# watch_v1_light-addon.net
KiCad netlist of a schematic drawn in EAGLE
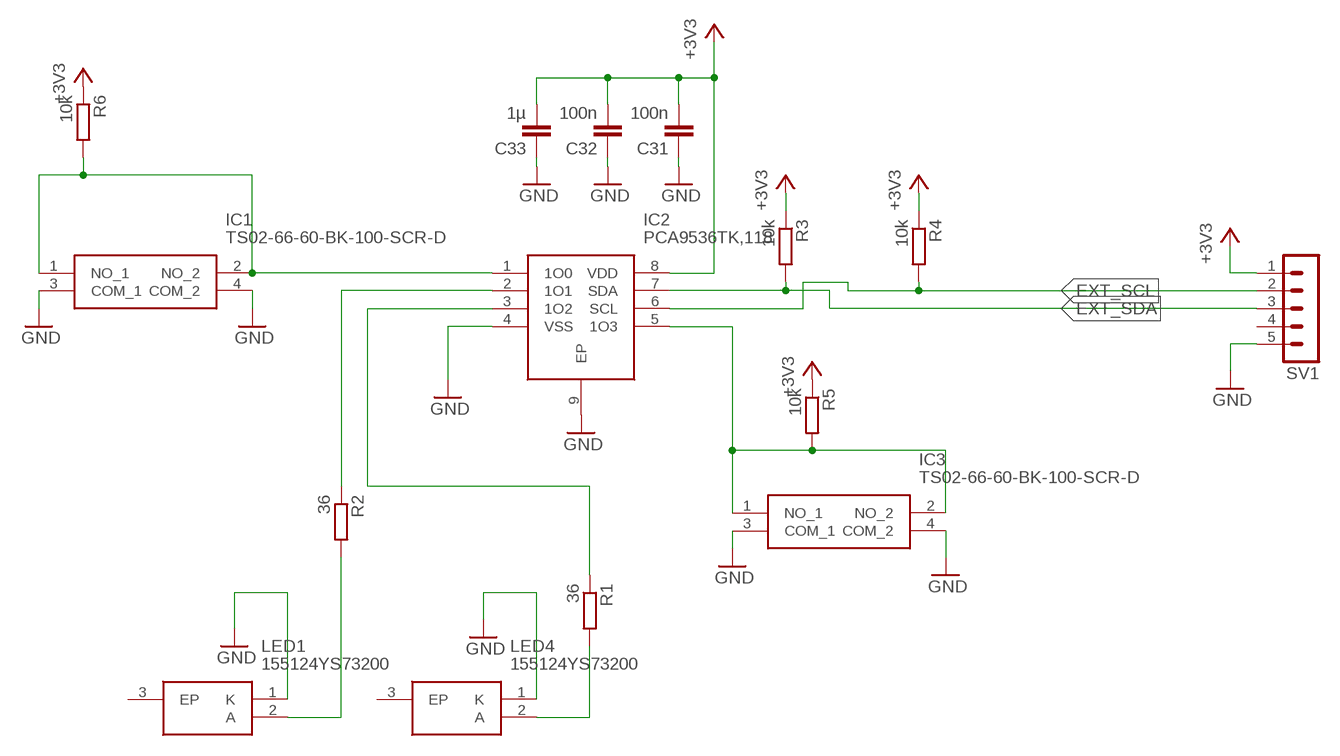
[diagram p0: schematic, sheet 1]

(export (version "E")
  (design (tool "Eeschema 10.0.6"))
  (components
    (comp (ref "C31")
      (value "100n")
      (footprint "eagle-import:C0402_S")
      (libsource (lib "eagle-import") (part "C0402_S"))
    )
    (comp (ref "C32")
      (value "100n")
      (footprint "eagle-import:C0402_S")
      (libsource (lib "eagle-import") (part "C0402_S"))
    )
    (comp (ref "C33")
      (value "1µ")
      (footprint "eagle-import:C0402_S")
      (libsource (lib "eagle-import") (part "C0402_S"))
    )
    (comp (ref "IC1")
      (value "TS02-66-60-BK-100-SCR-D")
      (footprint "eagle-import:TS026660BK100SCRD")
      (fields (field (name "MOUSER_PART_NUMBER") "179-TS026660BK100SCR"))
      (libsource (lib "eagle-import") (part "TS02-66-60-BK-100-SCR-D"))
    )
    (comp (ref "IC2")
      (value "PCA9536TK,118")
      (footprint "eagle-import:SON50P300X300X100-9N")
      (fields (field (name "MOUSER_PART_NUMBER") "771-PCA9536TK118"))
      (libsource (lib "eagle-import") (part "PCA9536TK,118"))
    )
    (comp (ref "IC3")
      (value "TS02-66-60-BK-100-SCR-D")
      (footprint "eagle-import:TS026660BK100SCRD")
      (fields (field (name "MOUSER_PART_NUMBER") "179-TS026660BK100SCR"))
      (libsource (lib "eagle-import") (part "TS02-66-60-BK-100-SCR-D"))
    )
    (comp (ref "LED1")
      (value "155124YS73200")
      (footprint "eagle-import:155124YS73200")
      (fields (field (name "MOUSER_PART_NUMBER") "710-155124YS73200"))
      (libsource (lib "eagle-import") (part "155124YS73200"))
    )
    (comp (ref "LED4")
      (value "155124YS73200")
      (footprint "eagle-import:155124YS73200")
      (fields (field (name "MOUSER_PART_NUMBER") "710-155124YS73200"))
      (libsource (lib "eagle-import") (part "155124YS73200"))
    )
    (comp (ref "R1")
      (value "36")
      (footprint "eagle-import:R0402")
      (libsource (lib "eagle-import") (part "R0402"))
    )
    (comp (ref "R2")
      (value "36")
      (footprint "eagle-import:R0402")
      (libsource (lib "eagle-import") (part "R0402"))
    )
    (comp (ref "R3")
      (value "10k")
      (footprint "eagle-import:R0402")
      (libsource (lib "eagle-import") (part "R0402"))
    )
    (comp (ref "R4")
      (value "10k")
      (footprint "eagle-import:R0402")
      (libsource (lib "eagle-import") (part "R0402"))
    )
    (comp (ref "R5")
      (value "10k")
      (footprint "eagle-import:R0402")
      (libsource (lib "eagle-import") (part "R0402"))
    )
    (comp (ref "R6")
      (value "10k")
      (footprint "eagle-import:R0402")
      (libsource (lib "eagle-import") (part "R0402"))
    )
    (comp (ref "SV1")
      (value "MA05-1")
      (footprint "eagle-import:MA05-1")
      (libsource (lib "eagle-import") (part "MA05-1"))
    )
  )
  (nets
    (net (code "1") (name "+3V3") (class "Default")
      (node (ref "C31") (pin "P$2") (pinfunction "2_P$2") (pintype "passive"))
      (node (ref "C32") (pin "P$2") (pinfunction "2_P$2") (pintype "passive"))
      (node (ref "C33") (pin "P$2") (pinfunction "2_P$2") (pintype "passive"))
      (node (ref "IC2") (pin "8") (pinfunction "VDD_8") (pintype "bidirectional"))
      (node (ref "R3") (pin "1") (pinfunction "1_1") (pintype "passive"))
      (node (ref "R4") (pin "1") (pinfunction "1_1") (pintype "passive"))
      (node (ref "R5") (pin "1") (pinfunction "1_1") (pintype "passive"))
      (node (ref "R6") (pin "1") (pinfunction "1_1") (pintype "passive"))
      (node (ref "SV1") (pin "1") (pinfunction "1_1") (pintype "passive"))
    )
    (net (code "2") (name "EXT_SCL") (class "Default")
      (node (ref "IC2") (pin "6") (pinfunction "SCL_6") (pintype "bidirectional"))
      (node (ref "R4") (pin "2") (pinfunction "2_2") (pintype "passive"))
      (node (ref "SV1") (pin "2") (pinfunction "2_2") (pintype "passive"))
    )
    (net (code "3") (name "EXT_SDA") (class "Default")
      (node (ref "IC2") (pin "7") (pinfunction "SDA_7") (pintype "bidirectional"))
      (node (ref "R3") (pin "2") (pinfunction "2_2") (pintype "passive"))
      (node (ref "SV1") (pin "3") (pinfunction "3_3") (pintype "passive"))
    )
    (net (code "4") (name "GND") (class "Default")
      (node (ref "C31") (pin "P$1") (pinfunction "1_P$1") (pintype "passive"))
      (node (ref "C32") (pin "P$1") (pinfunction "1_P$1") (pintype "passive"))
      (node (ref "C33") (pin "P$1") (pinfunction "1_P$1") (pintype "passive"))
      (node (ref "IC1") (pin "3") (pinfunction "COM_1_3") (pintype "bidirectional"))
      (node (ref "IC1") (pin "4") (pinfunction "COM_2_4") (pintype "bidirectional"))
      (node (ref "IC2") (pin "4") (pinfunction "VSS_4") (pintype "bidirectional"))
      (node (ref "IC2") (pin "9") (pinfunction "EP_9") (pintype "bidirectional"))
      (node (ref "IC3") (pin "3") (pinfunction "COM_1_3") (pintype "bidirectional"))
      (node (ref "IC3") (pin "4") (pinfunction "COM_2_4") (pintype "bidirectional"))
      (node (ref "LED1") (pin "1") (pinfunction "K_1") (pintype "bidirectional"))
      (node (ref "LED4") (pin "1") (pinfunction "K_1") (pintype "bidirectional"))
      (node (ref "SV1") (pin "5") (pinfunction "5_5") (pintype "passive"))
    )
    (net (code "5") (name "Net-(IC1-NO_1)") (class "Default")
      (node (ref "IC1") (pin "1") (pinfunction "NO_1_1") (pintype "bidirectional"))
      (node (ref "IC1") (pin "2") (pinfunction "NO_2_2") (pintype "bidirectional"))
      (node (ref "IC2") (pin "1") (pinfunction "1O0_1") (pintype "bidirectional"))
      (node (ref "R6") (pin "2") (pinfunction "2_2") (pintype "passive"))
    )
    (net (code "6") (name "Net-(IC2-1O1)") (class "Default")
      (node (ref "IC2") (pin "2") (pinfunction "1O1_2") (pintype "bidirectional"))
      (node (ref "R2") (pin "1") (pinfunction "1_1") (pintype "passive"))
    )
    (net (code "7") (name "Net-(IC2-1O2)") (class "Default")
      (node (ref "IC2") (pin "3") (pinfunction "1O2_3") (pintype "bidirectional"))
      (node (ref "R1") (pin "1") (pinfunction "1_1") (pintype "passive"))
    )
    (net (code "8") (name "Net-(IC2-1O3)") (class "Default")
      (node (ref "IC2") (pin "5") (pinfunction "1O3_5") (pintype "bidirectional"))
      (node (ref "IC3") (pin "1") (pinfunction "NO_1_1") (pintype "bidirectional"))
      (node (ref "IC3") (pin "2") (pinfunction "NO_2_2") (pintype "bidirectional"))
      (node (ref "R5") (pin "2") (pinfunction "2_2") (pintype "passive"))
    )
    (net (code "9") (name "Net-(LED1-A)") (class "Default")
      (node (ref "LED1") (pin "2") (pinfunction "A_2") (pintype "bidirectional"))
      (node (ref "R2") (pin "2") (pinfunction "2_2") (pintype "passive"))
    )
    (net (code "10") (name "Net-(LED4-A)") (class "Default")
      (node (ref "LED4") (pin "2") (pinfunction "A_2") (pintype "bidirectional"))
      (node (ref "R1") (pin "2") (pinfunction "2_2") (pintype "passive"))
    )
    (net (code "11") (name "unconnected-(LED1-EP-Pad3)") (class "Default")
      (node (ref "LED1") (pin "3") (pinfunction "EP_3") (pintype "bidirectional"))
    )
    (net (code "12") (name "unconnected-(LED4-EP-Pad3)") (class "Default")
      (node (ref "LED4") (pin "3") (pinfunction "EP_3") (pintype "bidirectional"))
    )
    (net (code "13") (name "unconnected-(SV1-Pad4)") (class "Default")
      (node (ref "SV1") (pin "4") (pinfunction "4_4") (pintype "passive"))
    )
  )
)
